# MidAdc.net
KiCad netlist of a schematic drawn in Altium Designer
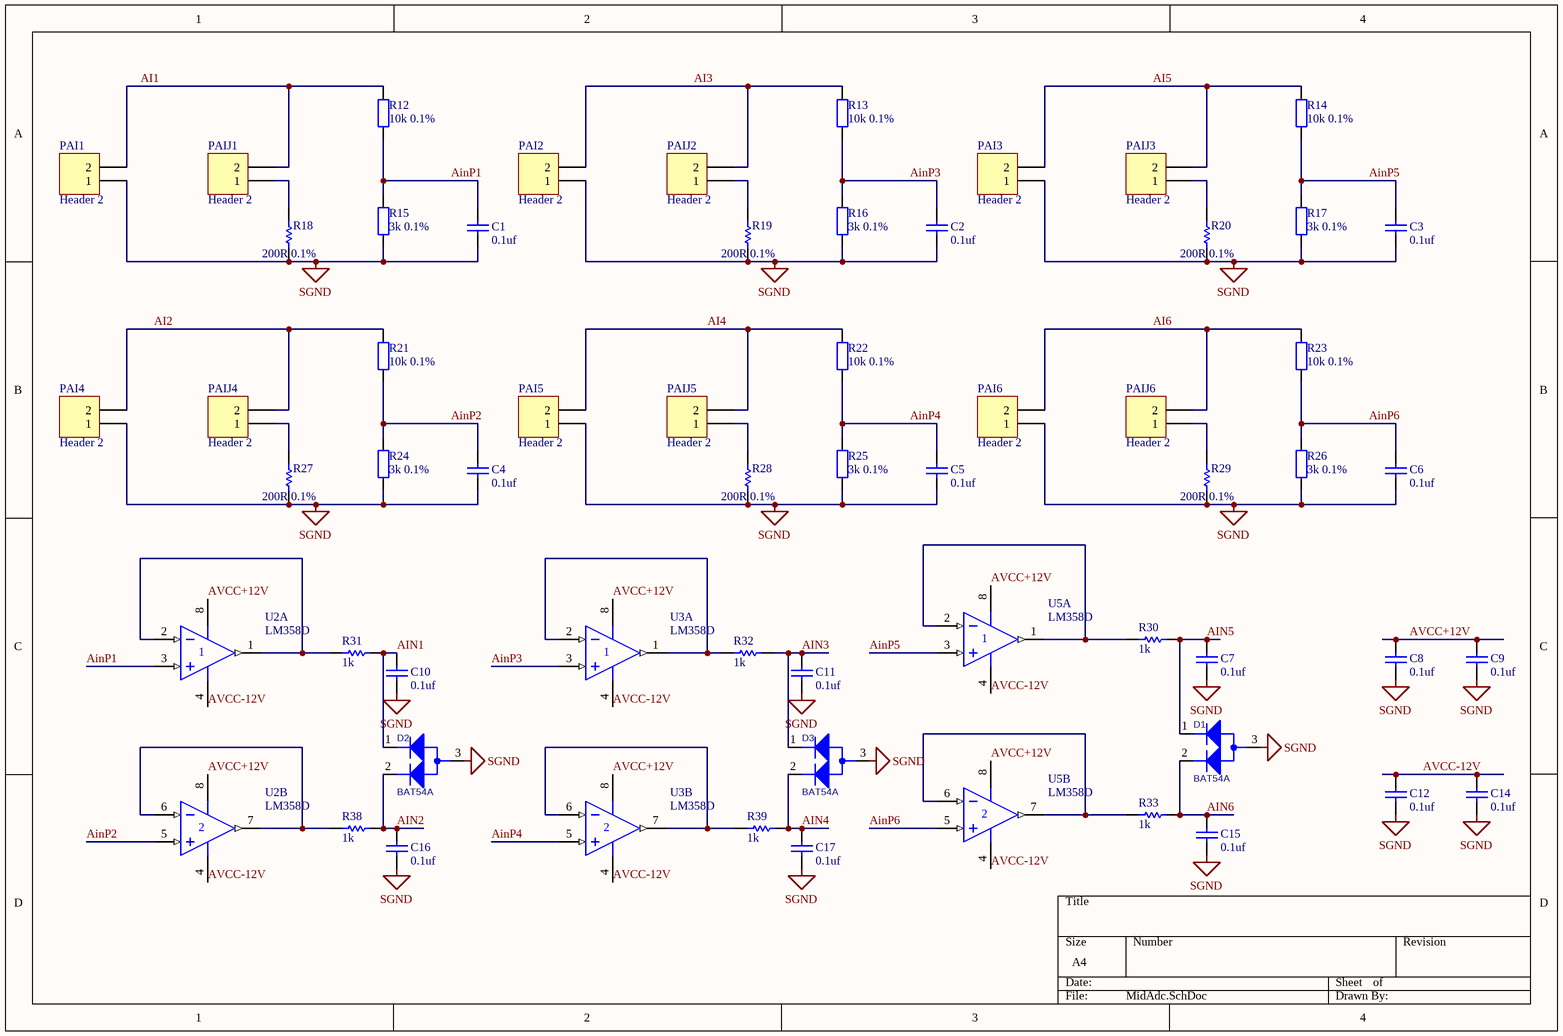
[diagram p0: MidAdc.SchDoc]

(export (version "E")
  (design (tool "Eeschema 10.0.6"))
  (components
    (comp (ref "C1")
      (value "0.1uf")
      (footprint "C0805")
      (description "Capacitor")
      (fields
        (field (name "MANUFACTURER") "Generic Components")
        (field (name "Comment") "Cap")
        (field (name "PUBLISHER") "Altium Hobart Technology Centre")
      )
      (libsource (lib "Miscellaneous Devices") (part "Cap"))
    )
    (comp (ref "C2")
      (value "0.1uf")
      (footprint "C0805")
      (description "Capacitor")
      (fields
        (field (name "MANUFACTURER") "Generic Components")
        (field (name "Comment") "Cap")
        (field (name "PUBLISHER") "Altium Hobart Technology Centre")
      )
      (libsource (lib "Miscellaneous Devices") (part "Cap"))
    )
    (comp (ref "C3")
      (value "0.1uf")
      (footprint "C0805")
      (description "Capacitor")
      (fields
        (field (name "MANUFACTURER") "Generic Components")
        (field (name "Comment") "Cap")
        (field (name "PUBLISHER") "Altium Hobart Technology Centre")
      )
      (libsource (lib "Miscellaneous Devices") (part "Cap"))
    )
    (comp (ref "C4")
      (value "0.1uf")
      (footprint "C0805")
      (description "Capacitor")
      (fields
        (field (name "MANUFACTURER") "Generic Components")
        (field (name "Comment") "Cap")
        (field (name "PUBLISHER") "Altium Hobart Technology Centre")
      )
      (libsource (lib "Miscellaneous Devices") (part "Cap"))
    )
    (comp (ref "C5")
      (value "0.1uf")
      (footprint "C0805")
      (description "Capacitor")
      (fields
        (field (name "MANUFACTURER") "Generic Components")
        (field (name "Comment") "Cap")
        (field (name "PUBLISHER") "Altium Hobart Technology Centre")
      )
      (libsource (lib "Miscellaneous Devices") (part "Cap"))
    )
    (comp (ref "C6")
      (value "0.1uf")
      (footprint "C0805")
      (description "Capacitor")
      (fields
        (field (name "MANUFACTURER") "Generic Components")
        (field (name "Comment") "Cap")
        (field (name "PUBLISHER") "Altium Hobart Technology Centre")
      )
      (libsource (lib "Miscellaneous Devices") (part "Cap"))
    )
    (comp (ref "C7")
      (value "0.1uf")
      (footprint "C0805")
      (description "Capacitor")
      (fields
        (field (name "MANUFACTURER") "Generic Components")
        (field (name "Comment") "Cap")
        (field (name "PUBLISHER") "Altium Hobart Technology Centre")
      )
      (libsource (lib "Miscellaneous Devices") (part "Cap"))
    )
    (comp (ref "C8")
      (value "0.1uf")
      (footprint "C0805")
      (description "Capacitor")
      (fields
        (field (name "MANUFACTURER") "Generic Components")
        (field (name "Comment") "Cap")
        (field (name "PUBLISHER") "Altium Hobart Technology Centre")
      )
      (libsource (lib "Miscellaneous Devices") (part "Cap"))
    )
    (comp (ref "C9")
      (value "0.1uf")
      (footprint "C0805")
      (description "Capacitor")
      (fields
        (field (name "MANUFACTURER") "Generic Components")
        (field (name "Comment") "Cap")
        (field (name "PUBLISHER") "Altium Hobart Technology Centre")
      )
      (libsource (lib "Miscellaneous Devices") (part "Cap"))
    )
    (comp (ref "C10")
      (value "0.1uf")
      (footprint "C0805")
      (description "Capacitor")
      (fields
        (field (name "MANUFACTURER") "Generic Components")
        (field (name "Comment") "Cap")
        (field (name "PUBLISHER") "Altium Hobart Technology Centre")
      )
      (libsource (lib "Miscellaneous Devices") (part "Cap"))
    )
    (comp (ref "C11")
      (value "0.1uf")
      (footprint "C0805")
      (description "Capacitor")
      (fields
        (field (name "MANUFACTURER") "Generic Components")
        (field (name "Comment") "Cap")
        (field (name "PUBLISHER") "Altium Hobart Technology Centre")
      )
      (libsource (lib "Miscellaneous Devices") (part "Cap"))
    )
    (comp (ref "C12")
      (value "0.1uf")
      (footprint "C0805")
      (description "Capacitor")
      (fields
        (field (name "MANUFACTURER") "Generic Components")
        (field (name "Comment") "Cap")
        (field (name "PUBLISHER") "Altium Hobart Technology Centre")
      )
      (libsource (lib "Miscellaneous Devices") (part "Cap"))
    )
    (comp (ref "C14")
      (value "0.1uf")
      (footprint "C0805")
      (description "Capacitor")
      (fields
        (field (name "MANUFACTURER") "Generic Components")
        (field (name "Comment") "Cap")
        (field (name "PUBLISHER") "Altium Hobart Technology Centre")
      )
      (libsource (lib "Miscellaneous Devices") (part "Cap"))
    )
    (comp (ref "C15")
      (value "0.1uf")
      (footprint "C0805")
      (description "Capacitor")
      (fields
        (field (name "MANUFACTURER") "Generic Components")
        (field (name "Comment") "Cap")
        (field (name "PUBLISHER") "Altium Hobart Technology Centre")
      )
      (libsource (lib "Miscellaneous Devices") (part "Cap"))
    )
    (comp (ref "C16")
      (value "0.1uf")
      (footprint "C0805")
      (description "Capacitor")
      (fields
        (field (name "MANUFACTURER") "Generic Components")
        (field (name "Comment") "Cap")
        (field (name "PUBLISHER") "Altium Hobart Technology Centre")
      )
      (libsource (lib "Miscellaneous Devices") (part "Cap"))
    )
    (comp (ref "C17")
      (value "0.1uf")
      (footprint "C0805")
      (description "Capacitor")
      (fields
        (field (name "MANUFACTURER") "Generic Components")
        (field (name "Comment") "Cap")
        (field (name "PUBLISHER") "Altium Hobart Technology Centre")
      )
      (libsource (lib "Miscellaneous Devices") (part "Cap"))
    )
    (comp (ref "D1") (value "BAT54A") (footprint "SOT23") (libsource (lib "*") (part "BAT54A/SOT_2")))
    (comp (ref "D2") (value "BAT54A") (footprint "SOT23") (libsource (lib "*") (part "BAT54A/SOT_2")))
    (comp (ref "D3") (value "BAT54A") (footprint "SOT23") (libsource (lib "*") (part "BAT54A/SOT_2")))
    (comp (ref "PAI1")
      (value "Header 2")
      (footprint "3.5-P2")
      (description "Header, 2-Pin")
      (fields (field (name "PUBLISHER") "Altium Limited"))
      (libsource (lib "Miscellaneous Connectors") (part "Header 2"))
    )
    (comp (ref "PAI2")
      (value "Header 2")
      (footprint "3.5-P2")
      (description "Header, 2-Pin")
      (fields (field (name "PUBLISHER") "Altium Limited"))
      (libsource (lib "Miscellaneous Connectors") (part "Header 2"))
    )
    (comp (ref "PAI3")
      (value "Header 2")
      (footprint "3.5-P2")
      (description "Header, 2-Pin")
      (fields (field (name "PUBLISHER") "Altium Limited"))
      (libsource (lib "Miscellaneous Connectors") (part "Header 2"))
    )
    (comp (ref "PAI4")
      (value "Header 2")
      (footprint "3.5-P2")
      (description "Header, 2-Pin")
      (fields (field (name "PUBLISHER") "Altium Limited"))
      (libsource (lib "Miscellaneous Connectors") (part "Header 2"))
    )
    (comp (ref "PAI5")
      (value "Header 2")
      (footprint "3.5-P2")
      (description "Header, 2-Pin")
      (fields (field (name "PUBLISHER") "Altium Limited"))
      (libsource (lib "Miscellaneous Connectors") (part "Header 2"))
    )
    (comp (ref "PAI6")
      (value "Header 2")
      (footprint "3.5-P2")
      (description "Header, 2-Pin")
      (fields (field (name "PUBLISHER") "Altium Limited"))
      (libsource (lib "Miscellaneous Connectors") (part "Header 2"))
    )
    (comp (ref "PAIJ1")
      (value "Header 2")
      (footprint "HDR1X2")
      (description "Header, 2-Pin")
      (fields (field (name "PUBLISHER") "Altium Limited"))
      (libsource (lib "Miscellaneous Connectors") (part "Header 2"))
    )
    (comp (ref "PAIJ2")
      (value "Header 2")
      (footprint "HDR1X2")
      (description "Header, 2-Pin")
      (fields (field (name "PUBLISHER") "Altium Limited"))
      (libsource (lib "Miscellaneous Connectors") (part "Header 2"))
    )
    (comp (ref "PAIJ3")
      (value "Header 2")
      (footprint "HDR1X2")
      (description "Header, 2-Pin")
      (fields (field (name "PUBLISHER") "Altium Limited"))
      (libsource (lib "Miscellaneous Connectors") (part "Header 2"))
    )
    (comp (ref "PAIJ4")
      (value "Header 2")
      (footprint "HDR1X2")
      (description "Header, 2-Pin")
      (fields (field (name "PUBLISHER") "Altium Limited"))
      (libsource (lib "Miscellaneous Connectors") (part "Header 2"))
    )
    (comp (ref "PAIJ5")
      (value "Header 2")
      (footprint "HDR1X2")
      (description "Header, 2-Pin")
      (fields (field (name "PUBLISHER") "Altium Limited"))
      (libsource (lib "Miscellaneous Connectors") (part "Header 2"))
    )
    (comp (ref "PAIJ6")
      (value "Header 2")
      (footprint "HDR1X2")
      (description "Header, 2-Pin")
      (fields (field (name "PUBLISHER") "Altium Limited"))
      (libsource (lib "Miscellaneous Connectors") (part "Header 2"))
    )
    (comp (ref "R12")
      (value "10k 0.1%")
      (footprint "0805")
      (fields (field (name "Comment") "Res2"))
      (libsource (lib "S1") (part "RES"))
    )
    (comp (ref "R13")
      (value "10k 0.1%")
      (footprint "0805")
      (fields (field (name "Comment") "Res2"))
      (libsource (lib "S1") (part "RES"))
    )
    (comp (ref "R14")
      (value "10k 0.1%")
      (footprint "0805")
      (fields (field (name "Comment") "Res2"))
      (libsource (lib "S1") (part "RES"))
    )
    (comp (ref "R15")
      (value "3k 0.1%")
      (footprint "0805")
      (fields (field (name "Comment") "Res2"))
      (libsource (lib "S1") (part "RES"))
    )
    (comp (ref "R16")
      (value "3k 0.1%")
      (footprint "0805")
      (fields (field (name "Comment") "Res2"))
      (libsource (lib "S1") (part "RES"))
    )
    (comp (ref "R17")
      (value "3k 0.1%")
      (footprint "0805")
      (fields (field (name "Comment") "Res2"))
      (libsource (lib "S1") (part "RES"))
    )
    (comp (ref "R18")
      (value "200R 0.1%")
      (footprint "0805")
      (description "Semiconductor Resistor")
      (fields (field (name "Comment") "Res Semi") (field (name "PUBLISHER") "Altium Limited"))
      (libsource (lib "Miscellaneous Devices") (part "Res Semi"))
    )
    (comp (ref "R19")
      (value "200R 0.1%")
      (footprint "0805")
      (description "Semiconductor Resistor")
      (fields (field (name "Comment") "Res Semi") (field (name "PUBLISHER") "Altium Limited"))
      (libsource (lib "Miscellaneous Devices") (part "Res Semi"))
    )
    (comp (ref "R20")
      (value "200R 0.1%")
      (footprint "0805")
      (description "Semiconductor Resistor")
      (fields (field (name "Comment") "Res Semi") (field (name "PUBLISHER") "Altium Limited"))
      (libsource (lib "Miscellaneous Devices") (part "Res Semi"))
    )
    (comp (ref "R21")
      (value "10k 0.1%")
      (footprint "0805")
      (fields (field (name "Comment") "Res2"))
      (libsource (lib "S1") (part "RES"))
    )
    (comp (ref "R22")
      (value "10k 0.1%")
      (footprint "0805")
      (fields (field (name "Comment") "Res2"))
      (libsource (lib "S1") (part "RES"))
    )
    (comp (ref "R23")
      (value "10k 0.1%")
      (footprint "0805")
      (fields (field (name "Comment") "Res2"))
      (libsource (lib "S1") (part "RES"))
    )
    (comp (ref "R24")
      (value "3k 0.1%")
      (footprint "0805")
      (fields (field (name "Comment") "Res2"))
      (libsource (lib "S1") (part "RES"))
    )
    (comp (ref "R25")
      (value "3k 0.1%")
      (footprint "0805")
      (fields (field (name "Comment") "Res2"))
      (libsource (lib "S1") (part "RES"))
    )
    (comp (ref "R26")
      (value "3k 0.1%")
      (footprint "0805")
      (fields (field (name "Comment") "Res2"))
      (libsource (lib "S1") (part "RES"))
    )
    (comp (ref "R27")
      (value "200R 0.1%")
      (footprint "0805")
      (description "Semiconductor Resistor")
      (fields (field (name "Comment") "Res Semi") (field (name "PUBLISHER") "Altium Limited"))
      (libsource (lib "Miscellaneous Devices") (part "Res Semi"))
    )
    (comp (ref "R28")
      (value "200R 0.1%")
      (footprint "0805")
      (description "Semiconductor Resistor")
      (fields (field (name "Comment") "Res Semi") (field (name "PUBLISHER") "Altium Limited"))
      (libsource (lib "Miscellaneous Devices") (part "Res Semi"))
    )
    (comp (ref "R29")
      (value "200R 0.1%")
      (footprint "0805")
      (description "Semiconductor Resistor")
      (fields (field (name "Comment") "Res Semi") (field (name "PUBLISHER") "Altium Limited"))
      (libsource (lib "Miscellaneous Devices") (part "Res Semi"))
    )
    (comp (ref "R30")
      (value "1k")
      (footprint "0805")
      (description "Semiconductor Resistor")
      (fields (field (name "Comment") "Res Semi") (field (name "PUBLISHER") "Altium Limited"))
      (libsource (lib "Miscellaneous Devices") (part "Res Semi"))
    )
    (comp (ref "R31")
      (value "1k")
      (footprint "0805")
      (description "Semiconductor Resistor")
      (fields (field (name "Comment") "Res Semi") (field (name "PUBLISHER") "Altium Limited"))
      (libsource (lib "Miscellaneous Devices") (part "Res Semi"))
    )
    (comp (ref "R32")
      (value "1k")
      (footprint "0805")
      (description "Semiconductor Resistor")
      (fields (field (name "Comment") "Res Semi") (field (name "PUBLISHER") "Altium Limited"))
      (libsource (lib "Miscellaneous Devices") (part "Res Semi"))
    )
    (comp (ref "R33")
      (value "1k")
      (footprint "0805")
      (description "Semiconductor Resistor")
      (fields (field (name "Comment") "Res Semi") (field (name "PUBLISHER") "Altium Limited"))
      (libsource (lib "Miscellaneous Devices") (part "Res Semi"))
    )
    (comp (ref "R38")
      (value "1k")
      (footprint "0805")
      (description "Semiconductor Resistor")
      (fields (field (name "Comment") "Res Semi") (field (name "PUBLISHER") "Altium Limited"))
      (libsource (lib "Miscellaneous Devices") (part "Res Semi"))
    )
    (comp (ref "R39")
      (value "1k")
      (footprint "0805")
      (description "Semiconductor Resistor")
      (fields (field (name "Comment") "Res Semi") (field (name "PUBLISHER") "Altium Limited"))
      (libsource (lib "Miscellaneous Devices") (part "Res Semi"))
    )
    (comp (ref "U2")
      (value "LM358D")
      (footprint "751-02_N")
      (description "Dual Low-Power Operational Amplifier")
      (fields (field (name "PUBLISHER") "Altium Limited"))
      (libsource (lib "Motorola Amplifier Operational Amplifier") (part "LM358D"))
    )
    (comp (ref "U3")
      (value "LM358D")
      (footprint "751-02_N")
      (description "Dual Low-Power Operational Amplifier")
      (fields (field (name "PUBLISHER") "Altium Limited"))
      (libsource (lib "Motorola Amplifier Operational Amplifier") (part "LM358D"))
    )
    (comp (ref "U5")
      (value "LM358D")
      (footprint "751-02_N")
      (description "Dual Low-Power Operational Amplifier")
      (fields (field (name "PUBLISHER") "Altium Limited"))
      (libsource (lib "Motorola Amplifier Operational Amplifier") (part "LM358D"))
    )
  )
  (nets
    (net (code "1") (name "/AI1") (class "Default")
      (node (ref "PAI1") (pin "2") (pinfunction "2_2") (pintype "passive"))
      (node (ref "PAIJ1") (pin "2") (pinfunction "2_2") (pintype "passive"))
      (node (ref "R12") (pin "1") (pinfunction "1_1") (pintype "passive"))
    )
    (net (code "2") (name "/AI2") (class "Default")
      (node (ref "PAI4") (pin "2") (pinfunction "2_2") (pintype "passive"))
      (node (ref "PAIJ4") (pin "2") (pinfunction "2_2") (pintype "passive"))
      (node (ref "R21") (pin "1") (pinfunction "1_1") (pintype "passive"))
    )
    (net (code "3") (name "/AI3") (class "Default")
      (node (ref "PAI2") (pin "2") (pinfunction "2_2") (pintype "passive"))
      (node (ref "PAIJ2") (pin "2") (pinfunction "2_2") (pintype "passive"))
      (node (ref "R13") (pin "1") (pinfunction "1_1") (pintype "passive"))
    )
    (net (code "4") (name "/AI4") (class "Default")
      (node (ref "PAI5") (pin "2") (pinfunction "2_2") (pintype "passive"))
      (node (ref "PAIJ5") (pin "2") (pinfunction "2_2") (pintype "passive"))
      (node (ref "R22") (pin "1") (pinfunction "1_1") (pintype "passive"))
    )
    (net (code "5") (name "/AI5") (class "Default")
      (node (ref "PAI3") (pin "2") (pinfunction "2_2") (pintype "passive"))
      (node (ref "PAIJ3") (pin "2") (pinfunction "2_2") (pintype "passive"))
      (node (ref "R14") (pin "1") (pinfunction "1_1") (pintype "passive"))
    )
    (net (code "6") (name "/AI6") (class "Default")
      (node (ref "PAI6") (pin "2") (pinfunction "2_2") (pintype "passive"))
      (node (ref "PAIJ6") (pin "2") (pinfunction "2_2") (pintype "passive"))
      (node (ref "R23") (pin "1") (pinfunction "1_1") (pintype "passive"))
    )
    (net (code "7") (name "/AIN1") (class "Default")
      (node (ref "C10") (pin "1") (pinfunction "1_1") (pintype "passive"))
      (node (ref "D2") (pin "1") (pinfunction "1_1") (pintype "passive"))
      (node (ref "R31") (pin "2") (pinfunction "2_2") (pintype "passive"))
    )
    (net (code "8") (name "/AIN2") (class "Default")
      (node (ref "C16") (pin "1") (pinfunction "1_1") (pintype "passive"))
      (node (ref "D2") (pin "2") (pinfunction "2_2") (pintype "passive"))
      (node (ref "R38") (pin "2") (pinfunction "2_2") (pintype "passive"))
    )
    (net (code "9") (name "/AIN3") (class "Default")
      (node (ref "C11") (pin "1") (pinfunction "1_1") (pintype "passive"))
      (node (ref "D3") (pin "1") (pinfunction "1_1") (pintype "passive"))
      (node (ref "R32") (pin "2") (pinfunction "2_2") (pintype "passive"))
    )
    (net (code "10") (name "/AIN4") (class "Default")
      (node (ref "C17") (pin "1") (pinfunction "1_1") (pintype "passive"))
      (node (ref "D3") (pin "2") (pinfunction "2_2") (pintype "passive"))
      (node (ref "R39") (pin "2") (pinfunction "2_2") (pintype "passive"))
    )
    (net (code "11") (name "/AIN5") (class "Default")
      (node (ref "C7") (pin "1") (pinfunction "1_1") (pintype "passive"))
      (node (ref "D1") (pin "1") (pinfunction "1_1") (pintype "passive"))
      (node (ref "R30") (pin "2") (pinfunction "2_2") (pintype "passive"))
    )
    (net (code "12") (name "/AIN6") (class "Default")
      (node (ref "C15") (pin "1") (pinfunction "1_1") (pintype "passive"))
      (node (ref "D1") (pin "2") (pinfunction "2_2") (pintype "passive"))
      (node (ref "R33") (pin "2") (pinfunction "2_2") (pintype "passive"))
    )
    (net (code "13") (name "/AVCC+12V") (class "Default")
      (node (ref "C8") (pin "1") (pinfunction "1_1") (pintype "passive"))
      (node (ref "C9") (pin "1") (pinfunction "1_1") (pintype "passive"))
      (node (ref "U2") (pin "8") (pinfunction "V+_8") (pintype "power_in"))
      (node (ref "U3") (pin "8") (pinfunction "V+_8") (pintype "power_in"))
      (node (ref "U5") (pin "8") (pinfunction "V+_8") (pintype "power_in"))
    )
    (net (code "14") (name "/AVCC-12V") (class "Default")
      (node (ref "C12") (pin "1") (pinfunction "1_1") (pintype "passive"))
      (node (ref "C14") (pin "1") (pinfunction "1_1") (pintype "passive"))
      (node (ref "U2") (pin "4") (pinfunction "V-_4") (pintype "power_in"))
      (node (ref "U3") (pin "4") (pinfunction "V-_4") (pintype "power_in"))
      (node (ref "U5") (pin "4") (pinfunction "V-_4") (pintype "power_in"))
    )
    (net (code "15") (name "/AinP1") (class "Default")
      (node (ref "C1") (pin "1") (pinfunction "1_1") (pintype "passive"))
      (node (ref "R12") (pin "2") (pinfunction "2_2") (pintype "passive"))
      (node (ref "R15") (pin "1") (pinfunction "1_1") (pintype "passive"))
      (node (ref "U2") (pin "3") (pinfunction "IN+_3") (pintype "input"))
    )
    (net (code "16") (name "/AinP2") (class "Default")
      (node (ref "C4") (pin "1") (pinfunction "1_1") (pintype "passive"))
      (node (ref "R21") (pin "2") (pinfunction "2_2") (pintype "passive"))
      (node (ref "R24") (pin "1") (pinfunction "1_1") (pintype "passive"))
      (node (ref "U2") (pin "5") (pinfunction "IN+_5") (pintype "input"))
    )
    (net (code "17") (name "/AinP3") (class "Default")
      (node (ref "C2") (pin "1") (pinfunction "1_1") (pintype "passive"))
      (node (ref "R13") (pin "2") (pinfunction "2_2") (pintype "passive"))
      (node (ref "R16") (pin "1") (pinfunction "1_1") (pintype "passive"))
      (node (ref "U3") (pin "3") (pinfunction "IN+_3") (pintype "input"))
    )
    (net (code "18") (name "/AinP4") (class "Default")
      (node (ref "C5") (pin "1") (pinfunction "1_1") (pintype "passive"))
      (node (ref "R22") (pin "2") (pinfunction "2_2") (pintype "passive"))
      (node (ref "R25") (pin "1") (pinfunction "1_1") (pintype "passive"))
      (node (ref "U3") (pin "5") (pinfunction "IN+_5") (pintype "input"))
    )
    (net (code "19") (name "/AinP5") (class "Default")
      (node (ref "C3") (pin "1") (pinfunction "1_1") (pintype "passive"))
      (node (ref "R14") (pin "2") (pinfunction "2_2") (pintype "passive"))
      (node (ref "R17") (pin "1") (pinfunction "1_1") (pintype "passive"))
      (node (ref "U5") (pin "3") (pinfunction "IN+_3") (pintype "input"))
    )
    (net (code "20") (name "/AinP6") (class "Default")
      (node (ref "C6") (pin "1") (pinfunction "1_1") (pintype "passive"))
      (node (ref "R23") (pin "2") (pinfunction "2_2") (pintype "passive"))
      (node (ref "R26") (pin "1") (pinfunction "1_1") (pintype "passive"))
      (node (ref "U5") (pin "5") (pinfunction "IN+_5") (pintype "input"))
    )
    (net (code "21") (name "Net-(PAIJ1-Pad1)") (class "Default")
      (node (ref "PAIJ1") (pin "1") (pinfunction "1_1") (pintype "passive"))
      (node (ref "R18") (pin "1") (pinfunction "1_1") (pintype "passive"))
    )
    (net (code "22") (name "Net-(PAIJ2-Pad1)") (class "Default")
      (node (ref "PAIJ2") (pin "1") (pinfunction "1_1") (pintype "passive"))
      (node (ref "R19") (pin "1") (pinfunction "1_1") (pintype "passive"))
    )
    (net (code "23") (name "Net-(PAIJ3-Pad1)") (class "Default")
      (node (ref "PAIJ3") (pin "1") (pinfunction "1_1") (pintype "passive"))
      (node (ref "R20") (pin "1") (pinfunction "1_1") (pintype "passive"))
    )
    (net (code "24") (name "Net-(PAIJ4-Pad1)") (class "Default")
      (node (ref "PAIJ4") (pin "1") (pinfunction "1_1") (pintype "passive"))
      (node (ref "R27") (pin "1") (pinfunction "1_1") (pintype "passive"))
    )
    (net (code "25") (name "Net-(PAIJ5-Pad1)") (class "Default")
      (node (ref "PAIJ5") (pin "1") (pinfunction "1_1") (pintype "passive"))
      (node (ref "R28") (pin "1") (pinfunction "1_1") (pintype "passive"))
    )
    (net (code "26") (name "Net-(PAIJ6-Pad1)") (class "Default")
      (node (ref "PAIJ6") (pin "1") (pinfunction "1_1") (pintype "passive"))
      (node (ref "R29") (pin "1") (pinfunction "1_1") (pintype "passive"))
    )
    (net (code "27") (name "Net-(U2A-IN-)") (class "Default")
      (node (ref "R31") (pin "1") (pinfunction "1_1") (pintype "passive"))
      (node (ref "U2") (pin "1") (pinfunction "OUT_1") (pintype "output"))
      (node (ref "U2") (pin "2") (pinfunction "IN-_2") (pintype "input"))
    )
    (net (code "28") (name "Net-(U2B-IN-)") (class "Default")
      (node (ref "R38") (pin "1") (pinfunction "1_1") (pintype "passive"))
      (node (ref "U2") (pin "6") (pinfunction "IN-_6") (pintype "input"))
      (node (ref "U2") (pin "7") (pinfunction "OUT_7") (pintype "output"))
    )
    (net (code "29") (name "Net-(U3A-IN-)") (class "Default")
      (node (ref "R32") (pin "1") (pinfunction "1_1") (pintype "passive"))
      (node (ref "U3") (pin "1") (pinfunction "OUT_1") (pintype "output"))
      (node (ref "U3") (pin "2") (pinfunction "IN-_2") (pintype "input"))
    )
    (net (code "30") (name "Net-(U3B-IN-)") (class "Default")
      (node (ref "R39") (pin "1") (pinfunction "1_1") (pintype "passive"))
      (node (ref "U3") (pin "6") (pinfunction "IN-_6") (pintype "input"))
      (node (ref "U3") (pin "7") (pinfunction "OUT_7") (pintype "output"))
    )
    (net (code "31") (name "Net-(U5A-IN-)") (class "Default")
      (node (ref "R30") (pin "1") (pinfunction "1_1") (pintype "passive"))
      (node (ref "U5") (pin "1") (pinfunction "OUT_1") (pintype "output"))
      (node (ref "U5") (pin "2") (pinfunction "IN-_2") (pintype "input"))
    )
    (net (code "32") (name "Net-(U5B-IN-)") (class "Default")
      (node (ref "R33") (pin "1") (pinfunction "1_1") (pintype "passive"))
      (node (ref "U5") (pin "6") (pinfunction "IN-_6") (pintype "input"))
      (node (ref "U5") (pin "7") (pinfunction "OUT_7") (pintype "output"))
    )
    (net (code "33") (name "SGND") (class "Default")
      (node (ref "C1") (pin "2") (pinfunction "2_2") (pintype "passive"))
      (node (ref "C10") (pin "2") (pinfunction "2_2") (pintype "passive"))
      (node (ref "C11") (pin "2") (pinfunction "2_2") (pintype "passive"))
      (node (ref "C12") (pin "2") (pinfunction "2_2") (pintype "passive"))
      (node (ref "C14") (pin "2") (pinfunction "2_2") (pintype "passive"))
      (node (ref "C15") (pin "2") (pinfunction "2_2") (pintype "passive"))
      (node (ref "C16") (pin "2") (pinfunction "2_2") (pintype "passive"))
      (node (ref "C17") (pin "2") (pinfunction "2_2") (pintype "passive"))
      (node (ref "C2") (pin "2") (pinfunction "2_2") (pintype "passive"))
      (node (ref "C3") (pin "2") (pinfunction "2_2") (pintype "passive"))
      (node (ref "C4") (pin "2") (pinfunction "2_2") (pintype "passive"))
      (node (ref "C5") (pin "2") (pinfunction "2_2") (pintype "passive"))
      (node (ref "C6") (pin "2") (pinfunction "2_2") (pintype "passive"))
      (node (ref "C7") (pin "2") (pinfunction "2_2") (pintype "passive"))
      (node (ref "C8") (pin "2") (pinfunction "2_2") (pintype "passive"))
      (node (ref "C9") (pin "2") (pinfunction "2_2") (pintype "passive"))
      (node (ref "D1") (pin "3") (pinfunction "3_3") (pintype "passive"))
      (node (ref "D2") (pin "3") (pinfunction "3_3") (pintype "passive"))
      (node (ref "D3") (pin "3") (pinfunction "3_3") (pintype "passive"))
      (node (ref "PAI1") (pin "1") (pinfunction "1_1") (pintype "passive"))
      (node (ref "PAI2") (pin "1") (pinfunction "1_1") (pintype "passive"))
      (node (ref "PAI3") (pin "1") (pinfunction "1_1") (pintype "passive"))
      (node (ref "PAI4") (pin "1") (pinfunction "1_1") (pintype "passive"))
      (node (ref "PAI5") (pin "1") (pinfunction "1_1") (pintype "passive"))
      (node (ref "PAI6") (pin "1") (pinfunction "1_1") (pintype "passive"))
      (node (ref "R15") (pin "2") (pinfunction "2_2") (pintype "passive"))
      (node (ref "R16") (pin "2") (pinfunction "2_2") (pintype "passive"))
      (node (ref "R17") (pin "2") (pinfunction "2_2") (pintype "passive"))
      (node (ref "R18") (pin "2") (pinfunction "2_2") (pintype "passive"))
      (node (ref "R19") (pin "2") (pinfunction "2_2") (pintype "passive"))
      (node (ref "R20") (pin "2") (pinfunction "2_2") (pintype "passive"))
      (node (ref "R24") (pin "2") (pinfunction "2_2") (pintype "passive"))
      (node (ref "R25") (pin "2") (pinfunction "2_2") (pintype "passive"))
      (node (ref "R26") (pin "2") (pinfunction "2_2") (pintype "passive"))
      (node (ref "R27") (pin "2") (pinfunction "2_2") (pintype "passive"))
      (node (ref "R28") (pin "2") (pinfunction "2_2") (pintype "passive"))
      (node (ref "R29") (pin "2") (pinfunction "2_2") (pintype "passive"))
    )
  )
)
